# dwm-breakout.net
KiCad netlist of a schematic drawn in EAGLE
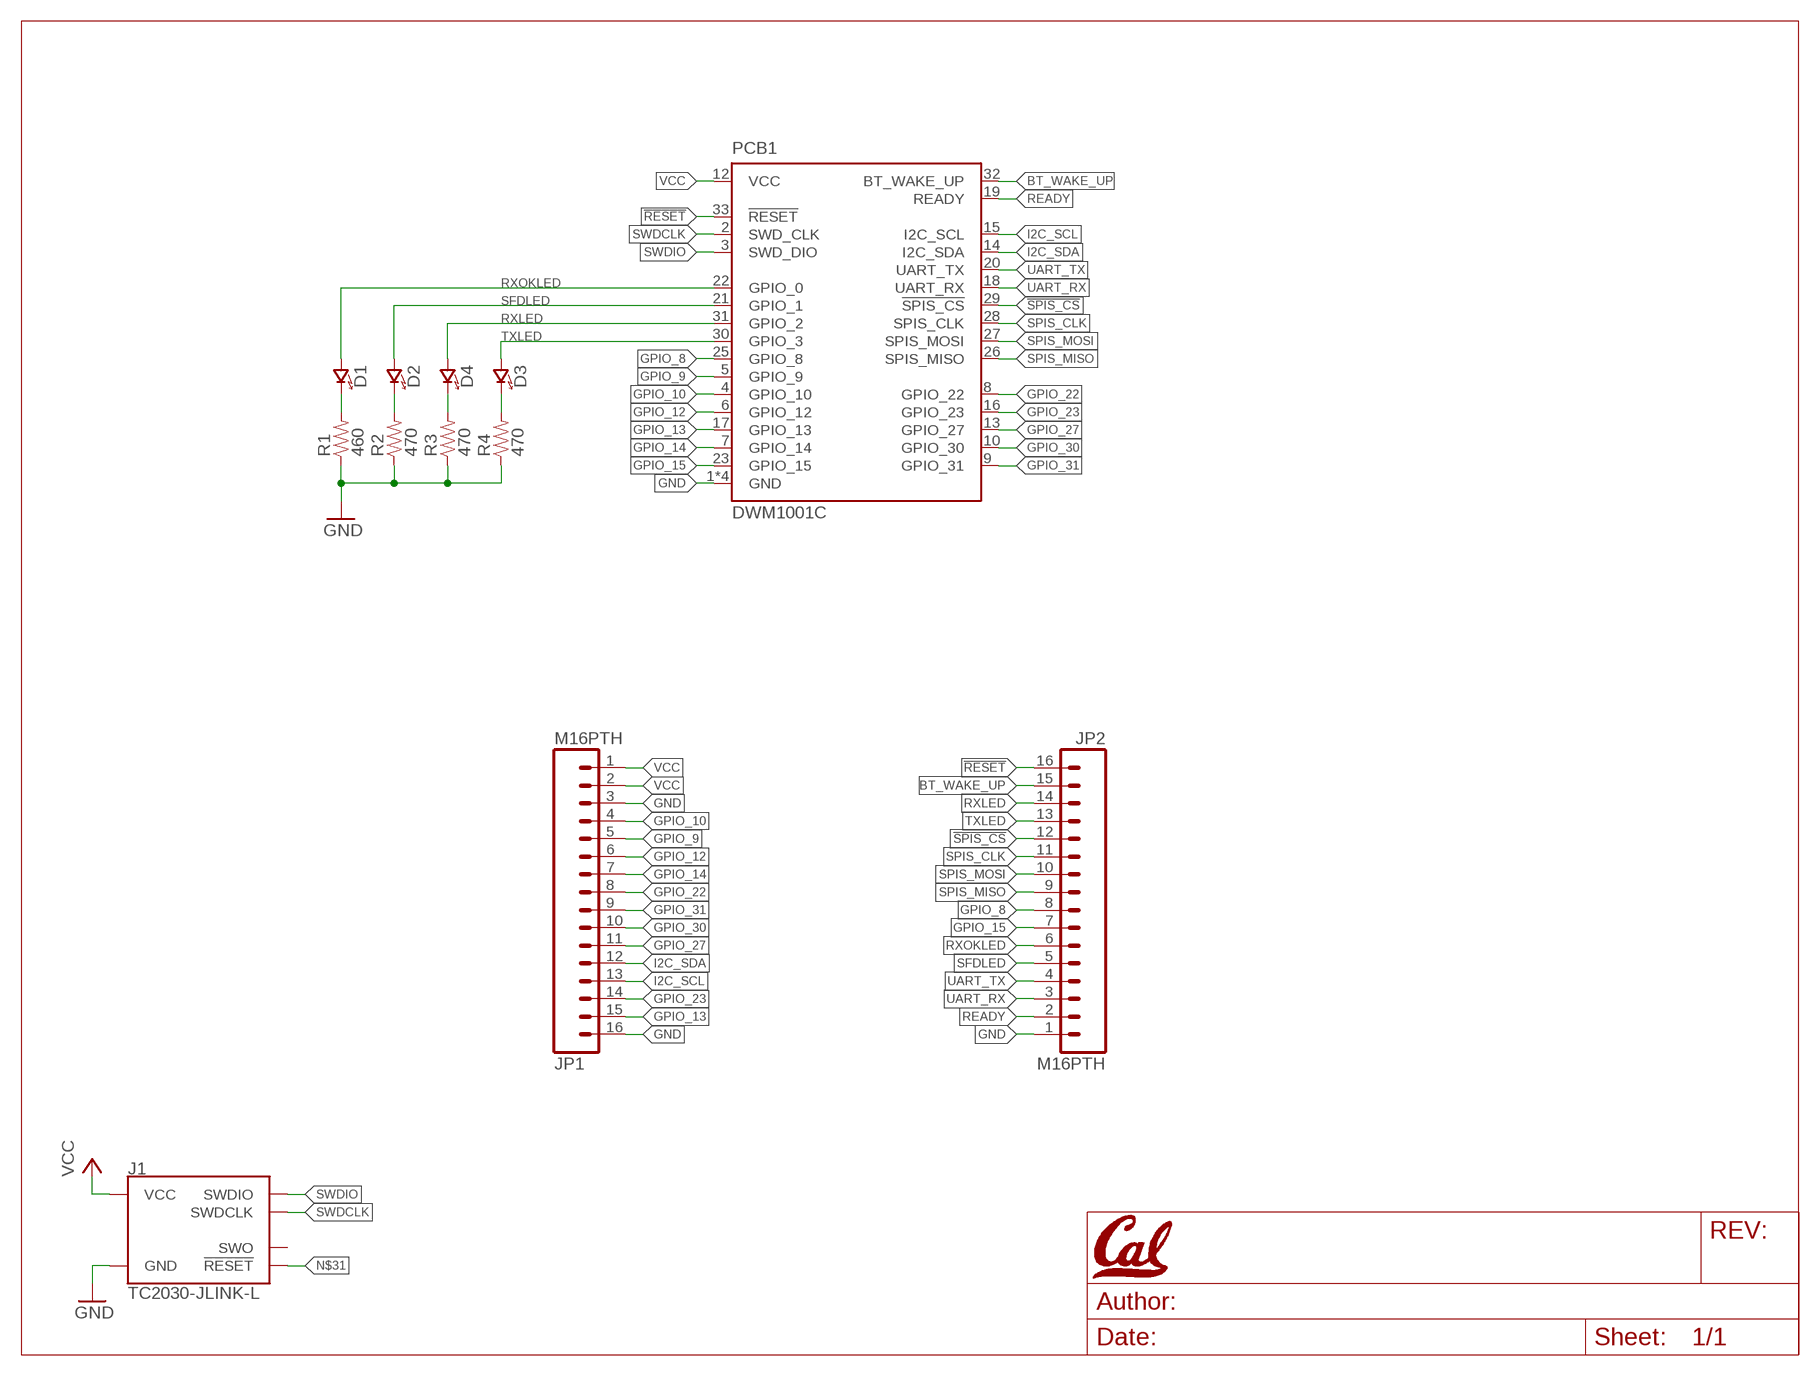
[diagram p0: schematic, sheet 1]

(export (version "E")
  (design (tool "Eeschema 10.0.6"))
  (components
    (comp (ref "D1")
      (value "LED0603")
      (footprint "eagle-import:LED-0603")
      (fields (field (name "MPN") "LTST-C104KRKT"))
      (libsource (lib "eagle-import") (part "LED0603"))
    )
    (comp (ref "D2")
      (value "LED0603")
      (footprint "eagle-import:LED-0603")
      (fields (field (name "MPN") "LTST-C194TBKT"))
      (libsource (lib "eagle-import") (part "LED0603"))
    )
    (comp (ref "D3")
      (value "LED0603")
      (footprint "eagle-import:LED-0603")
      (fields (field (name "MPN") "LTST-C190YKT"))
      (libsource (lib "eagle-import") (part "LED0603"))
    )
    (comp (ref "D4")
      (value "LED0603")
      (footprint "eagle-import:LED-0603")
      (fields (field (name "MPN") "LTST-C194KGKT"))
      (libsource (lib "eagle-import") (part "LED0603"))
    )
    (comp (ref "J1")
      (value "TC2030-JLINK-L")
      (footprint "eagle-import:TC2030-IDC")
      (libsource (lib "eagle-import") (part "TC2030-JLINK-L"))
    )
    (comp (ref "JP1")
      (value "M16PTH")
      (footprint "eagle-import:1X16")
      (libsource (lib "eagle-import") (part "M16PTH"))
    )
    (comp (ref "JP2")
      (value "M16PTH")
      (footprint "eagle-import:1X16")
      (libsource (lib "eagle-import") (part "M16PTH"))
    )
    (comp (ref "PCB1")
      (value "DWM1001C")
      (footprint "eagle-import:DWM1001C")
      (libsource (lib "eagle-import") (part "DWM1001C"))
    )
    (comp (ref "R1")
      (value "460")
      (footprint "eagle-import:0402_RES")
      (fields (field (name "MPN") "MCR01MZPJ471"))
      (libsource (lib "eagle-import") (part "RESISTOR0402_RES"))
    )
    (comp (ref "R2")
      (value "470")
      (footprint "eagle-import:0402_RES")
      (fields (field (name "MPN") "MCR01MZPJ471"))
      (libsource (lib "eagle-import") (part "RESISTOR0402_RES"))
    )
    (comp (ref "R3")
      (value "470")
      (footprint "eagle-import:0402_RES")
      (fields (field (name "MPN") "MCR01MZPJ471"))
      (libsource (lib "eagle-import") (part "RESISTOR0402_RES"))
    )
    (comp (ref "R4")
      (value "470")
      (footprint "eagle-import:0402_RES")
      (fields (field (name "MPN") "MCR01MZPJ471"))
      (libsource (lib "eagle-import") (part "RESISTOR0402_RES"))
    )
  )
  (nets
    (net (code "1") (name "/~{RESET}") (class "Default")
      (node (ref "JP2") (pin "16") (pinfunction "16_16") (pintype "passive"))
      (node (ref "PCB1") (pin "33") (pinfunction "~{RESET}_33") (pintype "bidirectional"))
    )
    (net (code "2") (name "/~{SPIS_CS}") (class "Default")
      (node (ref "JP2") (pin "12") (pinfunction "12_12") (pintype "passive"))
      (node (ref "PCB1") (pin "29") (pinfunction "~{SPIS_CS}_29") (pintype "bidirectional"))
    )
    (net (code "3") (name "BT_WAKE_UP") (class "Default")
      (node (ref "JP2") (pin "15") (pinfunction "15_15") (pintype "passive"))
      (node (ref "PCB1") (pin "32") (pinfunction "BT_WAKE_UP_32") (pintype "bidirectional"))
    )
    (net (code "4") (name "GND") (class "Default")
      (node (ref "J1") (pin "5") (pinfunction "GND_5") (pintype "bidirectional"))
      (node (ref "JP1") (pin "16") (pinfunction "16_16") (pintype "passive"))
      (node (ref "JP1") (pin "3") (pinfunction "3_3") (pintype "passive"))
      (node (ref "JP2") (pin "1") (pinfunction "1_1") (pintype "passive"))
      (node (ref "PCB1") (pin "1") (pinfunction "GND_1") (pintype "bidirectional"))
      (node (ref "PCB1") (pin "11") (pinfunction "GND_11") (pintype "bidirectional"))
      (node (ref "PCB1") (pin "24") (pinfunction "GND_24") (pintype "bidirectional"))
      (node (ref "PCB1") (pin "34") (pinfunction "GND_34") (pintype "bidirectional"))
      (node (ref "R1") (pin "1") (pinfunction "1_1") (pintype "passive"))
      (node (ref "R2") (pin "1") (pinfunction "1_1") (pintype "passive"))
      (node (ref "R3") (pin "1") (pinfunction "1_1") (pintype "passive"))
      (node (ref "R4") (pin "1") (pinfunction "1_1") (pintype "passive"))
    )
    (net (code "5") (name "GPIO_8") (class "Default")
      (node (ref "JP2") (pin "8") (pinfunction "8_8") (pintype "passive"))
      (node (ref "PCB1") (pin "25") (pinfunction "GPIO_8_25") (pintype "bidirectional"))
    )
    (net (code "6") (name "GPIO_9") (class "Default")
      (node (ref "JP1") (pin "5") (pinfunction "5_5") (pintype "passive"))
      (node (ref "PCB1") (pin "5") (pinfunction "GPIO_9_5") (pintype "bidirectional"))
    )
    (net (code "7") (name "GPIO_10") (class "Default")
      (node (ref "JP1") (pin "4") (pinfunction "4_4") (pintype "passive"))
      (node (ref "PCB1") (pin "4") (pinfunction "GPIO_10_4") (pintype "bidirectional"))
    )
    (net (code "8") (name "GPIO_12") (class "Default")
      (node (ref "JP1") (pin "6") (pinfunction "6_6") (pintype "passive"))
      (node (ref "PCB1") (pin "6") (pinfunction "GPIO_12_6") (pintype "bidirectional"))
    )
    (net (code "9") (name "GPIO_13") (class "Default")
      (node (ref "JP1") (pin "15") (pinfunction "15_15") (pintype "passive"))
      (node (ref "PCB1") (pin "17") (pinfunction "GPIO_13_17") (pintype "bidirectional"))
    )
    (net (code "10") (name "GPIO_14") (class "Default")
      (node (ref "JP1") (pin "7") (pinfunction "7_7") (pintype "passive"))
      (node (ref "PCB1") (pin "7") (pinfunction "GPIO_14_7") (pintype "bidirectional"))
    )
    (net (code "11") (name "GPIO_15") (class "Default")
      (node (ref "JP2") (pin "7") (pinfunction "7_7") (pintype "passive"))
      (node (ref "PCB1") (pin "23") (pinfunction "GPIO_15_23") (pintype "bidirectional"))
    )
    (net (code "12") (name "GPIO_22") (class "Default")
      (node (ref "JP1") (pin "8") (pinfunction "8_8") (pintype "passive"))
      (node (ref "PCB1") (pin "8") (pinfunction "GPIO_22_8") (pintype "bidirectional"))
    )
    (net (code "13") (name "GPIO_23") (class "Default")
      (node (ref "JP1") (pin "14") (pinfunction "14_14") (pintype "passive"))
      (node (ref "PCB1") (pin "16") (pinfunction "GPIO_23_16") (pintype "bidirectional"))
    )
    (net (code "14") (name "GPIO_27") (class "Default")
      (node (ref "JP1") (pin "11") (pinfunction "11_11") (pintype "passive"))
      (node (ref "PCB1") (pin "13") (pinfunction "GPIO_27_13") (pintype "bidirectional"))
    )
    (net (code "15") (name "GPIO_30") (class "Default")
      (node (ref "JP1") (pin "10") (pinfunction "10_10") (pintype "passive"))
      (node (ref "PCB1") (pin "10") (pinfunction "GPIO_30_10") (pintype "bidirectional"))
    )
    (net (code "16") (name "GPIO_31") (class "Default")
      (node (ref "JP1") (pin "9") (pinfunction "9_9") (pintype "passive"))
      (node (ref "PCB1") (pin "9") (pinfunction "GPIO_31_9") (pintype "bidirectional"))
    )
    (net (code "17") (name "I2C_SCL") (class "Default")
      (node (ref "JP1") (pin "13") (pinfunction "13_13") (pintype "passive"))
      (node (ref "PCB1") (pin "15") (pinfunction "I2C_SCL_15") (pintype "bidirectional"))
    )
    (net (code "18") (name "I2C_SDA") (class "Default")
      (node (ref "JP1") (pin "12") (pinfunction "12_12") (pintype "passive"))
      (node (ref "PCB1") (pin "14") (pinfunction "I2C_SDA_14") (pintype "bidirectional"))
    )
    (net (code "19") (name "N$31") (class "Default")
      (node (ref "J1") (pin "3") (pinfunction "~{RESET}_3") (pintype "bidirectional"))
    )
    (net (code "20") (name "Net-(D1-CATHODE)") (class "Default")
      (node (ref "D1") (pin "C") (pinfunction "CATHODE_C") (pintype "bidirectional"))
      (node (ref "R1") (pin "2") (pinfunction "2_2") (pintype "passive"))
    )
    (net (code "21") (name "Net-(D2-CATHODE)") (class "Default")
      (node (ref "D2") (pin "C") (pinfunction "CATHODE_C") (pintype "bidirectional"))
      (node (ref "R2") (pin "2") (pinfunction "2_2") (pintype "passive"))
    )
    (net (code "22") (name "Net-(D3-CATHODE)") (class "Default")
      (node (ref "D3") (pin "C") (pinfunction "CATHODE_C") (pintype "bidirectional"))
      (node (ref "R4") (pin "2") (pinfunction "2_2") (pintype "passive"))
    )
    (net (code "23") (name "Net-(D4-CATHODE)") (class "Default")
      (node (ref "D4") (pin "C") (pinfunction "CATHODE_C") (pintype "bidirectional"))
      (node (ref "R3") (pin "2") (pinfunction "2_2") (pintype "passive"))
    )
    (net (code "24") (name "READY") (class "Default")
      (node (ref "JP2") (pin "2") (pinfunction "2_2") (pintype "passive"))
      (node (ref "PCB1") (pin "19") (pinfunction "READY_19") (pintype "bidirectional"))
    )
    (net (code "25") (name "RXLED") (class "Default")
      (node (ref "D4") (pin "A") (pinfunction "ANODE_A") (pintype "bidirectional"))
      (node (ref "JP2") (pin "14") (pinfunction "14_14") (pintype "passive"))
      (node (ref "PCB1") (pin "31") (pinfunction "GPIO_2_31") (pintype "bidirectional"))
    )
    (net (code "26") (name "RXOKLED") (class "Default")
      (node (ref "D1") (pin "A") (pinfunction "ANODE_A") (pintype "bidirectional"))
      (node (ref "JP2") (pin "6") (pinfunction "6_6") (pintype "passive"))
      (node (ref "PCB1") (pin "22") (pinfunction "GPIO_0_22") (pintype "bidirectional"))
    )
    (net (code "27") (name "SFDLED") (class "Default")
      (node (ref "D2") (pin "A") (pinfunction "ANODE_A") (pintype "bidirectional"))
      (node (ref "JP2") (pin "5") (pinfunction "5_5") (pintype "passive"))
      (node (ref "PCB1") (pin "21") (pinfunction "GPIO_1_21") (pintype "bidirectional"))
    )
    (net (code "28") (name "SPIS_CLK") (class "Default")
      (node (ref "JP2") (pin "11") (pinfunction "11_11") (pintype "passive"))
      (node (ref "PCB1") (pin "28") (pinfunction "SPIS_CLK_28") (pintype "bidirectional"))
    )
    (net (code "29") (name "SPIS_MISO") (class "Default")
      (node (ref "JP2") (pin "9") (pinfunction "9_9") (pintype "passive"))
      (node (ref "PCB1") (pin "26") (pinfunction "SPIS_MISO_26") (pintype "bidirectional"))
    )
    (net (code "30") (name "SPIS_MOSI") (class "Default")
      (node (ref "JP2") (pin "10") (pinfunction "10_10") (pintype "passive"))
      (node (ref "PCB1") (pin "27") (pinfunction "SPIS_MOSI_27") (pintype "bidirectional"))
    )
    (net (code "31") (name "SWDCLK") (class "Default")
      (node (ref "J1") (pin "4") (pinfunction "SWDCLK_4") (pintype "bidirectional"))
      (node (ref "PCB1") (pin "2") (pinfunction "SWD_CLK_2") (pintype "bidirectional"))
    )
    (net (code "32") (name "SWDIO") (class "Default")
      (node (ref "J1") (pin "2") (pinfunction "SWDIO_2") (pintype "bidirectional"))
      (node (ref "PCB1") (pin "3") (pinfunction "SWD_DIO_3") (pintype "bidirectional"))
    )
    (net (code "33") (name "TXLED") (class "Default")
      (node (ref "D3") (pin "A") (pinfunction "ANODE_A") (pintype "bidirectional"))
      (node (ref "JP2") (pin "13") (pinfunction "13_13") (pintype "passive"))
      (node (ref "PCB1") (pin "30") (pinfunction "GPIO_3_30") (pintype "bidirectional"))
    )
    (net (code "34") (name "UART_RX") (class "Default")
      (node (ref "JP2") (pin "3") (pinfunction "3_3") (pintype "passive"))
      (node (ref "PCB1") (pin "18") (pinfunction "UART_RX_18") (pintype "bidirectional"))
    )
    (net (code "35") (name "UART_TX") (class "Default")
      (node (ref "JP2") (pin "4") (pinfunction "4_4") (pintype "passive"))
      (node (ref "PCB1") (pin "20") (pinfunction "UART_TX_20") (pintype "bidirectional"))
    )
    (net (code "36") (name "VCC") (class "Default")
      (node (ref "J1") (pin "1") (pinfunction "VCC_1") (pintype "bidirectional"))
      (node (ref "JP1") (pin "1") (pinfunction "1_1") (pintype "passive"))
      (node (ref "JP1") (pin "2") (pinfunction "2_2") (pintype "passive"))
      (node (ref "PCB1") (pin "12") (pinfunction "VCC_12") (pintype "bidirectional"))
    )
    (net (code "37") (name "unconnected-(J1-SWO-Pad6)") (class "Default")
      (node (ref "J1") (pin "6") (pinfunction "SWO_6") (pintype "bidirectional"))
    )
  )
)
